# tick-mk-1_1.net
KiCad netlist of a schematic drawn in EAGLE
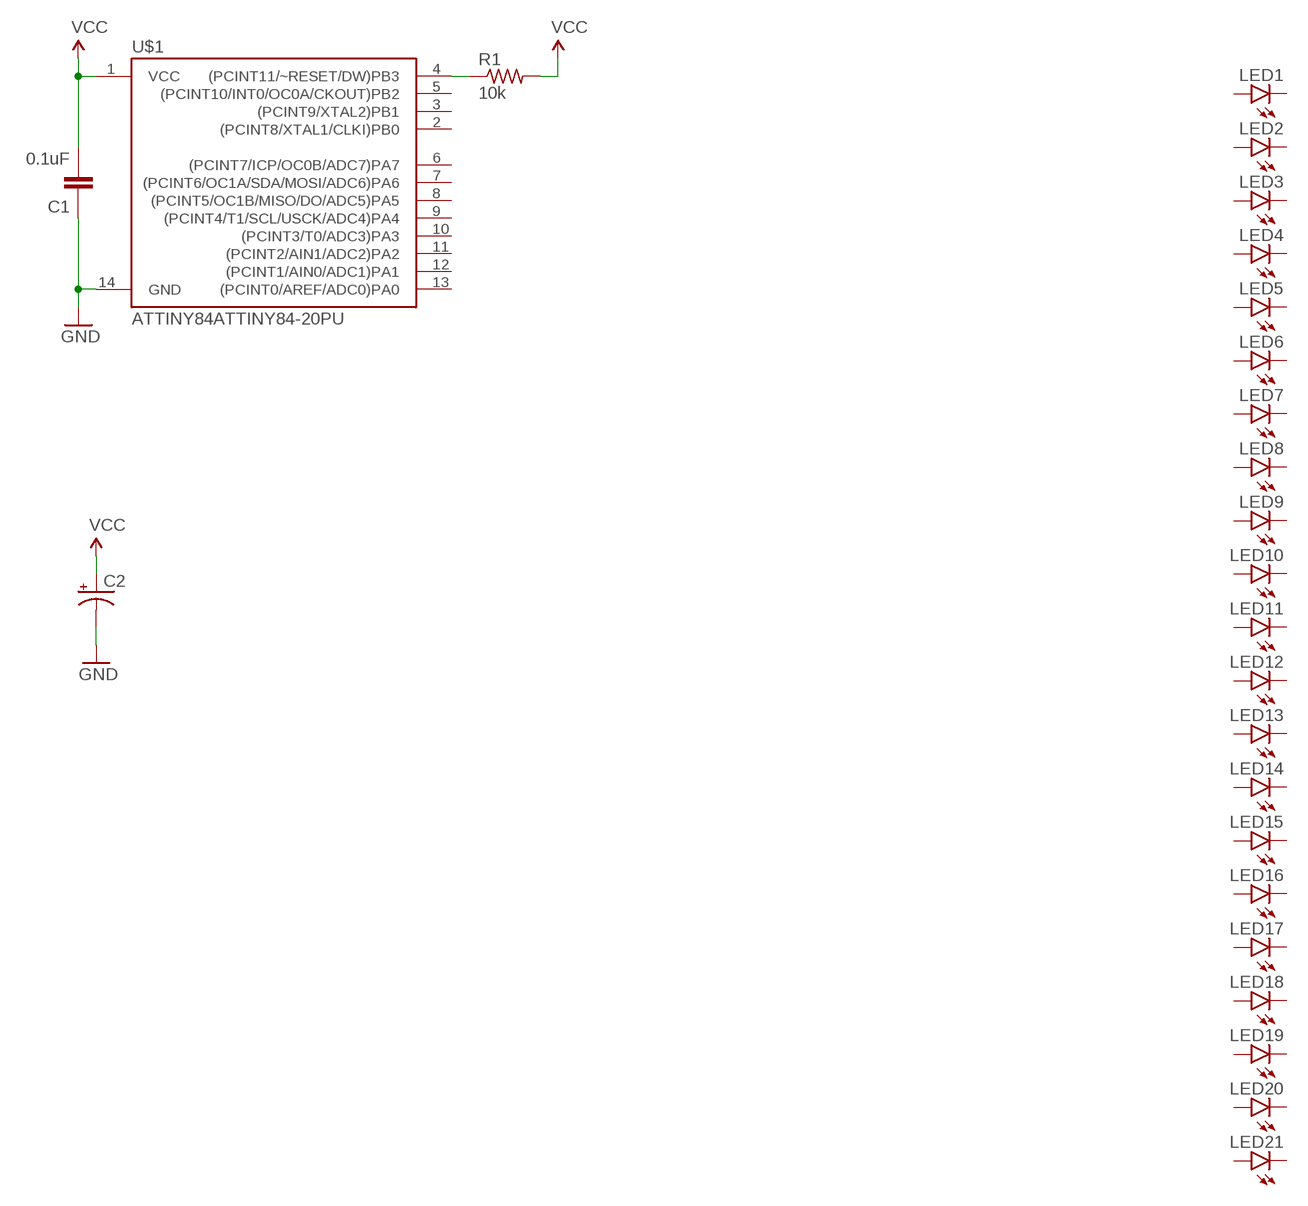
[diagram p0: schematic, sheet 1]

(export (version "E")
  (design (tool "Eeschema 10.0.6"))
  (components
    (comp (ref "C1")
      (value "0.1uF")
      (footprint "eagle-import:C025-024X044")
      (libsource (lib "eagle-import") (part "CAPACITOR-CERAMIC025-024X044"))
    )
    (comp (ref "C2")
      (value "CAPACITOR-POLARIZEDE2-5")
      (footprint "eagle-import:E2-5")
      (libsource (lib "eagle-import") (part "CAPACITOR-POLARIZEDE2-5"))
    )
    (comp (ref "LED1")
      (value "LED5MM_SHORTPADS")
      (footprint "eagle-import:LED5MM_SHORTPADS")
      (libsource (lib "eagle-import") (part "LED5MM_SHORTPADS"))
    )
    (comp (ref "LED2")
      (value "LED5MM_SHORTPADS")
      (footprint "eagle-import:LED5MM_SHORTPADS")
      (libsource (lib "eagle-import") (part "LED5MM_SHORTPADS"))
    )
    (comp (ref "LED3")
      (value "LED5MM_SHORTPADS")
      (footprint "eagle-import:LED5MM_SHORTPADS")
      (libsource (lib "eagle-import") (part "LED5MM_SHORTPADS"))
    )
    (comp (ref "LED4")
      (value "LED5MM_SHORTPADS")
      (footprint "eagle-import:LED5MM_SHORTPADS")
      (libsource (lib "eagle-import") (part "LED5MM_SHORTPADS"))
    )
    (comp (ref "LED5")
      (value "LED5MM_SHORTPADS")
      (footprint "eagle-import:LED5MM_SHORTPADS")
      (libsource (lib "eagle-import") (part "LED5MM_SHORTPADS"))
    )
    (comp (ref "LED6")
      (value "LED5MM_SHORTPADS")
      (footprint "eagle-import:LED5MM_SHORTPADS")
      (libsource (lib "eagle-import") (part "LED5MM_SHORTPADS"))
    )
    (comp (ref "LED7")
      (value "LED5MM_SHORTPADS")
      (footprint "eagle-import:LED5MM_SHORTPADS")
      (libsource (lib "eagle-import") (part "LED5MM_SHORTPADS"))
    )
    (comp (ref "LED8")
      (value "LED5MM_SHORTPADS")
      (footprint "eagle-import:LED5MM_SHORTPADS")
      (libsource (lib "eagle-import") (part "LED5MM_SHORTPADS"))
    )
    (comp (ref "LED9")
      (value "LED5MM_SHORTPADS")
      (footprint "eagle-import:LED5MM_SHORTPADS")
      (libsource (lib "eagle-import") (part "LED5MM_SHORTPADS"))
    )
    (comp (ref "LED10")
      (value "LED5MM_SHORTPADS")
      (footprint "eagle-import:LED5MM_SHORTPADS")
      (libsource (lib "eagle-import") (part "LED5MM_SHORTPADS"))
    )
    (comp (ref "LED11")
      (value "LED5MM_SHORTPADS")
      (footprint "eagle-import:LED5MM_SHORTPADS")
      (libsource (lib "eagle-import") (part "LED5MM_SHORTPADS"))
    )
    (comp (ref "LED12")
      (value "LED5MM_SHORTPADS")
      (footprint "eagle-import:LED5MM_SHORTPADS")
      (libsource (lib "eagle-import") (part "LED5MM_SHORTPADS"))
    )
    (comp (ref "LED13")
      (value "LED5MM_SHORTPADS")
      (footprint "eagle-import:LED5MM_SHORTPADS")
      (libsource (lib "eagle-import") (part "LED5MM_SHORTPADS"))
    )
    (comp (ref "LED14")
      (value "LED5MM_SHORTPADS")
      (footprint "eagle-import:LED5MM_SHORTPADS")
      (libsource (lib "eagle-import") (part "LED5MM_SHORTPADS"))
    )
    (comp (ref "LED15")
      (value "LED5MM_SHORTPADS")
      (footprint "eagle-import:LED5MM_SHORTPADS")
      (libsource (lib "eagle-import") (part "LED5MM_SHORTPADS"))
    )
    (comp (ref "LED16")
      (value "LED5MM_SHORTPADS")
      (footprint "eagle-import:LED5MM_SHORTPADS")
      (libsource (lib "eagle-import") (part "LED5MM_SHORTPADS"))
    )
    (comp (ref "LED17")
      (value "LED5MM_SHORTPADS")
      (footprint "eagle-import:LED5MM_SHORTPADS")
      (libsource (lib "eagle-import") (part "LED5MM_SHORTPADS"))
    )
    (comp (ref "LED18")
      (value "LED5MM_SHORTPADS")
      (footprint "eagle-import:LED5MM_SHORTPADS")
      (libsource (lib "eagle-import") (part "LED5MM_SHORTPADS"))
    )
    (comp (ref "LED19")
      (value "LED5MM_SHORTPADS")
      (footprint "eagle-import:LED5MM_SHORTPADS")
      (libsource (lib "eagle-import") (part "LED5MM_SHORTPADS"))
    )
    (comp (ref "LED20")
      (value "LED5MM_SHORTPADS")
      (footprint "eagle-import:LED5MM_SHORTPADS")
      (libsource (lib "eagle-import") (part "LED5MM_SHORTPADS"))
    )
    (comp (ref "LED21")
      (value "LED5MM_SHORTPADS")
      (footprint "eagle-import:LED5MM_SHORTPADS")
      (libsource (lib "eagle-import") (part "LED5MM_SHORTPADS"))
    )
    (comp (ref "R1")
      (value "10k")
      (footprint "eagle-import:RESISTOR-AXIAL-PTH-5.08MM")
      (libsource (lib "eagle-import") (part "RESISTORPTH-AXIAL-5.08MM"))
    )
    (comp (ref "U$1")
      (value "ATTINY84ATTINY84-20PU")
      (footprint "eagle-import:DIL14")
      (libsource (lib "eagle-import") (part "ATTINY84ATTINY84-20PU"))
    )
  )
  (nets
    (net (code "1") (name "GND") (class "Default")
      (node (ref "C1") (pin "1") (pinfunction "1_1") (pintype "passive"))
      (node (ref "C2") (pin "-") (pinfunction "-_-") (pintype "passive"))
      (node (ref "U$1") (pin "14") (pinfunction "GND_14") (pintype "bidirectional"))
    )
    (net (code "2") (name "Net-(R1-1)") (class "Default")
      (node (ref "R1") (pin "P$1") (pinfunction "1_P$1") (pintype "passive"))
      (node (ref "U$1") (pin "4") (pinfunction "(PCINT11/~{RESET/DW})PB3_4") (pintype "bidirectional"))
    )
    (net (code "3") (name "VCC") (class "Default")
      (node (ref "C1") (pin "2") (pinfunction "2_2") (pintype "passive"))
      (node (ref "C2") (pin "+") (pinfunction "+_+") (pintype "passive"))
      (node (ref "R1") (pin "P$2") (pinfunction "2_P$2") (pintype "passive"))
      (node (ref "U$1") (pin "1") (pinfunction "VCC_1") (pintype "bidirectional"))
    )
    (net (code "4") (name "unconnected-(LED1-C-PadK)") (class "Default")
      (node (ref "LED1") (pin "K") (pinfunction "C_K") (pintype "passive"))
    )
    (net (code "5") (name "unconnected-(LED1-PadA)") (class "Default")
      (node (ref "LED1") (pin "A") (pinfunction "A_A") (pintype "passive"))
    )
    (net (code "6") (name "unconnected-(LED2-C-PadK)") (class "Default")
      (node (ref "LED2") (pin "K") (pinfunction "C_K") (pintype "passive"))
    )
    (net (code "7") (name "unconnected-(LED2-PadA)") (class "Default")
      (node (ref "LED2") (pin "A") (pinfunction "A_A") (pintype "passive"))
    )
    (net (code "8") (name "unconnected-(LED3-C-PadK)") (class "Default")
      (node (ref "LED3") (pin "K") (pinfunction "C_K") (pintype "passive"))
    )
    (net (code "9") (name "unconnected-(LED3-PadA)") (class "Default")
      (node (ref "LED3") (pin "A") (pinfunction "A_A") (pintype "passive"))
    )
    (net (code "10") (name "unconnected-(LED4-C-PadK)") (class "Default")
      (node (ref "LED4") (pin "K") (pinfunction "C_K") (pintype "passive"))
    )
    (net (code "11") (name "unconnected-(LED4-PadA)") (class "Default")
      (node (ref "LED4") (pin "A") (pinfunction "A_A") (pintype "passive"))
    )
    (net (code "12") (name "unconnected-(LED5-C-PadK)") (class "Default")
      (node (ref "LED5") (pin "K") (pinfunction "C_K") (pintype "passive"))
    )
    (net (code "13") (name "unconnected-(LED5-PadA)") (class "Default")
      (node (ref "LED5") (pin "A") (pinfunction "A_A") (pintype "passive"))
    )
    (net (code "14") (name "unconnected-(LED6-C-PadK)") (class "Default")
      (node (ref "LED6") (pin "K") (pinfunction "C_K") (pintype "passive"))
    )
    (net (code "15") (name "unconnected-(LED6-PadA)") (class "Default")
      (node (ref "LED6") (pin "A") (pinfunction "A_A") (pintype "passive"))
    )
    (net (code "16") (name "unconnected-(LED7-C-PadK)") (class "Default")
      (node (ref "LED7") (pin "K") (pinfunction "C_K") (pintype "passive"))
    )
    (net (code "17") (name "unconnected-(LED7-PadA)") (class "Default")
      (node (ref "LED7") (pin "A") (pinfunction "A_A") (pintype "passive"))
    )
    (net (code "18") (name "unconnected-(LED8-C-PadK)") (class "Default")
      (node (ref "LED8") (pin "K") (pinfunction "C_K") (pintype "passive"))
    )
    (net (code "19") (name "unconnected-(LED8-PadA)") (class "Default")
      (node (ref "LED8") (pin "A") (pinfunction "A_A") (pintype "passive"))
    )
    (net (code "20") (name "unconnected-(LED9-C-PadK)") (class "Default")
      (node (ref "LED9") (pin "K") (pinfunction "C_K") (pintype "passive"))
    )
    (net (code "21") (name "unconnected-(LED9-PadA)") (class "Default")
      (node (ref "LED9") (pin "A") (pinfunction "A_A") (pintype "passive"))
    )
    (net (code "22") (name "unconnected-(LED10-C-PadK)") (class "Default")
      (node (ref "LED10") (pin "K") (pinfunction "C_K") (pintype "passive"))
    )
    (net (code "23") (name "unconnected-(LED10-PadA)") (class "Default")
      (node (ref "LED10") (pin "A") (pinfunction "A_A") (pintype "passive"))
    )
    (net (code "24") (name "unconnected-(LED11-C-PadK)") (class "Default")
      (node (ref "LED11") (pin "K") (pinfunction "C_K") (pintype "passive"))
    )
    (net (code "25") (name "unconnected-(LED11-PadA)") (class "Default")
      (node (ref "LED11") (pin "A") (pinfunction "A_A") (pintype "passive"))
    )
    (net (code "26") (name "unconnected-(LED12-C-PadK)") (class "Default")
      (node (ref "LED12") (pin "K") (pinfunction "C_K") (pintype "passive"))
    )
    (net (code "27") (name "unconnected-(LED12-PadA)") (class "Default")
      (node (ref "LED12") (pin "A") (pinfunction "A_A") (pintype "passive"))
    )
    (net (code "28") (name "unconnected-(LED13-C-PadK)") (class "Default")
      (node (ref "LED13") (pin "K") (pinfunction "C_K") (pintype "passive"))
    )
    (net (code "29") (name "unconnected-(LED13-PadA)") (class "Default")
      (node (ref "LED13") (pin "A") (pinfunction "A_A") (pintype "passive"))
    )
    (net (code "30") (name "unconnected-(LED14-C-PadK)") (class "Default")
      (node (ref "LED14") (pin "K") (pinfunction "C_K") (pintype "passive"))
    )
    (net (code "31") (name "unconnected-(LED14-PadA)") (class "Default")
      (node (ref "LED14") (pin "A") (pinfunction "A_A") (pintype "passive"))
    )
    (net (code "32") (name "unconnected-(LED15-C-PadK)") (class "Default")
      (node (ref "LED15") (pin "K") (pinfunction "C_K") (pintype "passive"))
    )
    (net (code "33") (name "unconnected-(LED15-PadA)") (class "Default")
      (node (ref "LED15") (pin "A") (pinfunction "A_A") (pintype "passive"))
    )
    (net (code "34") (name "unconnected-(LED16-C-PadK)") (class "Default")
      (node (ref "LED16") (pin "K") (pinfunction "C_K") (pintype "passive"))
    )
    (net (code "35") (name "unconnected-(LED16-PadA)") (class "Default")
      (node (ref "LED16") (pin "A") (pinfunction "A_A") (pintype "passive"))
    )
    (net (code "36") (name "unconnected-(LED17-C-PadK)") (class "Default")
      (node (ref "LED17") (pin "K") (pinfunction "C_K") (pintype "passive"))
    )
    (net (code "37") (name "unconnected-(LED17-PadA)") (class "Default")
      (node (ref "LED17") (pin "A") (pinfunction "A_A") (pintype "passive"))
    )
    (net (code "38") (name "unconnected-(LED18-C-PadK)") (class "Default")
      (node (ref "LED18") (pin "K") (pinfunction "C_K") (pintype "passive"))
    )
    (net (code "39") (name "unconnected-(LED18-PadA)") (class "Default")
      (node (ref "LED18") (pin "A") (pinfunction "A_A") (pintype "passive"))
    )
    (net (code "40") (name "unconnected-(LED19-C-PadK)") (class "Default")
      (node (ref "LED19") (pin "K") (pinfunction "C_K") (pintype "passive"))
    )
    (net (code "41") (name "unconnected-(LED19-PadA)") (class "Default")
      (node (ref "LED19") (pin "A") (pinfunction "A_A") (pintype "passive"))
    )
    (net (code "42") (name "unconnected-(LED20-C-PadK)") (class "Default")
      (node (ref "LED20") (pin "K") (pinfunction "C_K") (pintype "passive"))
    )
    (net (code "43") (name "unconnected-(LED20-PadA)") (class "Default")
      (node (ref "LED20") (pin "A") (pinfunction "A_A") (pintype "passive"))
    )
    (net (code "44") (name "unconnected-(LED21-C-PadK)") (class "Default")
      (node (ref "LED21") (pin "K") (pinfunction "C_K") (pintype "passive"))
    )
    (net (code "45") (name "unconnected-(LED21-PadA)") (class "Default")
      (node (ref "LED21") (pin "A") (pinfunction "A_A") (pintype "passive"))
    )
    (net (code "46") (name "unconnected-(U$1-(PCINT0{slash}AREF{slash}ADC0)PA0-Pad13)") (class "Default")
      (node (ref "U$1") (pin "13") (pinfunction "(PCINT0/AREF/ADC0)PA0_13") (pintype "bidirectional"))
    )
    (net (code "47") (name "unconnected-(U$1-(PCINT1{slash}AIN0{slash}ADC1)PA1-Pad12)") (class "Default")
      (node (ref "U$1") (pin "12") (pinfunction "(PCINT1/AIN0/ADC1)PA1_12") (pintype "bidirectional"))
    )
    (net (code "48") (name "unconnected-(U$1-(PCINT2{slash}AIN1{slash}ADC2)PA2-Pad11)") (class "Default")
      (node (ref "U$1") (pin "11") (pinfunction "(PCINT2/AIN1/ADC2)PA2_11") (pintype "bidirectional"))
    )
    (net (code "49") (name "unconnected-(U$1-(PCINT3{slash}T0{slash}ADC3)PA3-Pad10)") (class "Default")
      (node (ref "U$1") (pin "10") (pinfunction "(PCINT3/T0/ADC3)PA3_10") (pintype "bidirectional"))
    )
    (net (code "50") (name "unconnected-(U$1-(PCINT4{slash}T1{slash}SCL{slash}USCK{slash}ADC4)PA4-Pad9)") (class "Default")
      (node (ref "U$1") (pin "9") (pinfunction "(PCINT4/T1/SCL/USCK/ADC4)PA4_9") (pintype "bidirectional"))
    )
    (net (code "51") (name "unconnected-(U$1-(PCINT5{slash}OC1B{slash}MISO{slash}DO{slash}ADC5)PA5-Pad8)") (class "Default")
      (node (ref "U$1") (pin "8") (pinfunction "(PCINT5/OC1B/MISO/DO/ADC5)PA5_8") (pintype "bidirectional"))
    )
    (net (code "52") (name "unconnected-(U$1-(PCINT6{slash}OC1A{slash}SDA{slash}MOSI{slash}ADC6)PA6-Pad7)") (class "Default")
      (node (ref "U$1") (pin "7") (pinfunction "(PCINT6/OC1A/SDA/MOSI/ADC6)PA6_7") (pintype "bidirectional"))
    )
    (net (code "53") (name "unconnected-(U$1-(PCINT7{slash}ICP{slash}OC0B{slash}ADC7)PA7-Pad6)") (class "Default")
      (node (ref "U$1") (pin "6") (pinfunction "(PCINT7/ICP/OC0B/ADC7)PA7_6") (pintype "bidirectional"))
    )
    (net (code "54") (name "unconnected-(U$1-(PCINT8{slash}XTAL1{slash}CLKI)PB0-Pad2)") (class "Default")
      (node (ref "U$1") (pin "2") (pinfunction "(PCINT8/XTAL1/CLKI)PB0_2") (pintype "bidirectional"))
    )
    (net (code "55") (name "unconnected-(U$1-(PCINT9{slash}XTAL2)PB1-Pad3)") (class "Default")
      (node (ref "U$1") (pin "3") (pinfunction "(PCINT9/XTAL2)PB1_3") (pintype "bidirectional"))
    )
    (net (code "56") (name "unconnected-(U$1-(PCINT10{slash}INT0{slash}OC0A{slash}CKOUT)PB2-Pad5)") (class "Default")
      (node (ref "U$1") (pin "5") (pinfunction "(PCINT10/INT0/OC0A/CKOUT)PB2_5") (pintype "bidirectional"))
    )
  )
)
